# core.net
KiCad netlist of a schematic drawn in Altium Designer
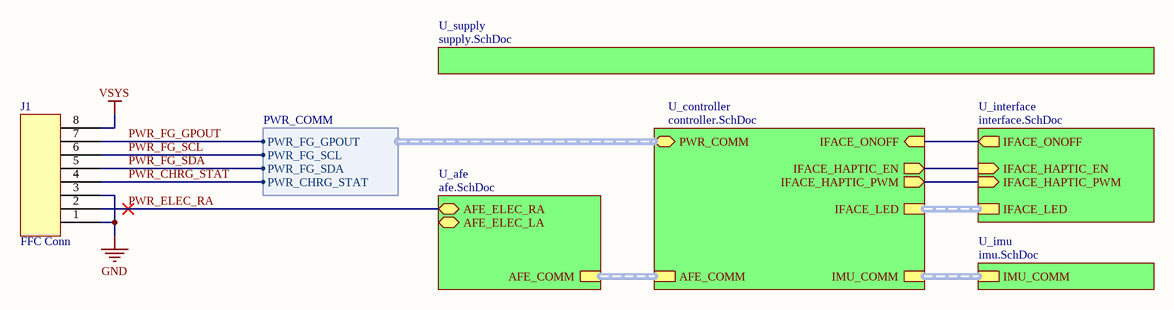
[diagram p0: core.SchDoc]

(export (version "E")
  (design (tool "Eeschema 10.0.6"))
  (components
    (comp (ref "J1")
      (value "FFC Conn")
      (footprint "WE68610814122")
      (description "Conn - FFC, 8 Pin, 1 mm Pitch, Top Contacts, SMD, Right Angle, Slide Lock")
      (libsource (lib "ecg-go") (part "WE68610814122"))
    )
  )
  (nets
    (net (code "4") (name "/AFE_ELEC_RA") (class "Default")
      (node (ref "J1") (pin "2") (pinfunction "2_2") (pintype "passive"))
    )
    (net (code "10") (name "/PWR_CHRG_STAT") (class "Default")
      (node (ref "J1") (pin "4") (pinfunction "4_4") (pintype "passive"))
    )
    (net (code "12") (name "/PWR_FG_GPOUT") (class "Default")
      (node (ref "J1") (pin "7") (pinfunction "7_7") (pintype "passive"))
    )
    (net (code "13") (name "/PWR_FG_SCL") (class "Default")
      (node (ref "J1") (pin "6") (pinfunction "6_6") (pintype "passive"))
    )
    (net (code "14") (name "/PWR_FG_SDA") (class "Default")
      (node (ref "J1") (pin "5") (pinfunction "5_5") (pintype "passive"))
    )
    (net (code "16") (name "GND") (class "Default")
      (node (ref "J1") (pin "1") (pinfunction "1_1") (pintype "passive"))
      (node (ref "J1") (pin "3") (pinfunction "3_3") (pintype "passive"))
    )
    (net (code "17") (name "VSYS") (class "Default")
      (node (ref "J1") (pin "8") (pinfunction "8_8") (pintype "passive"))
    )
  )
)
